# Power.net
KiCad netlist of a schematic drawn in Altium Designer
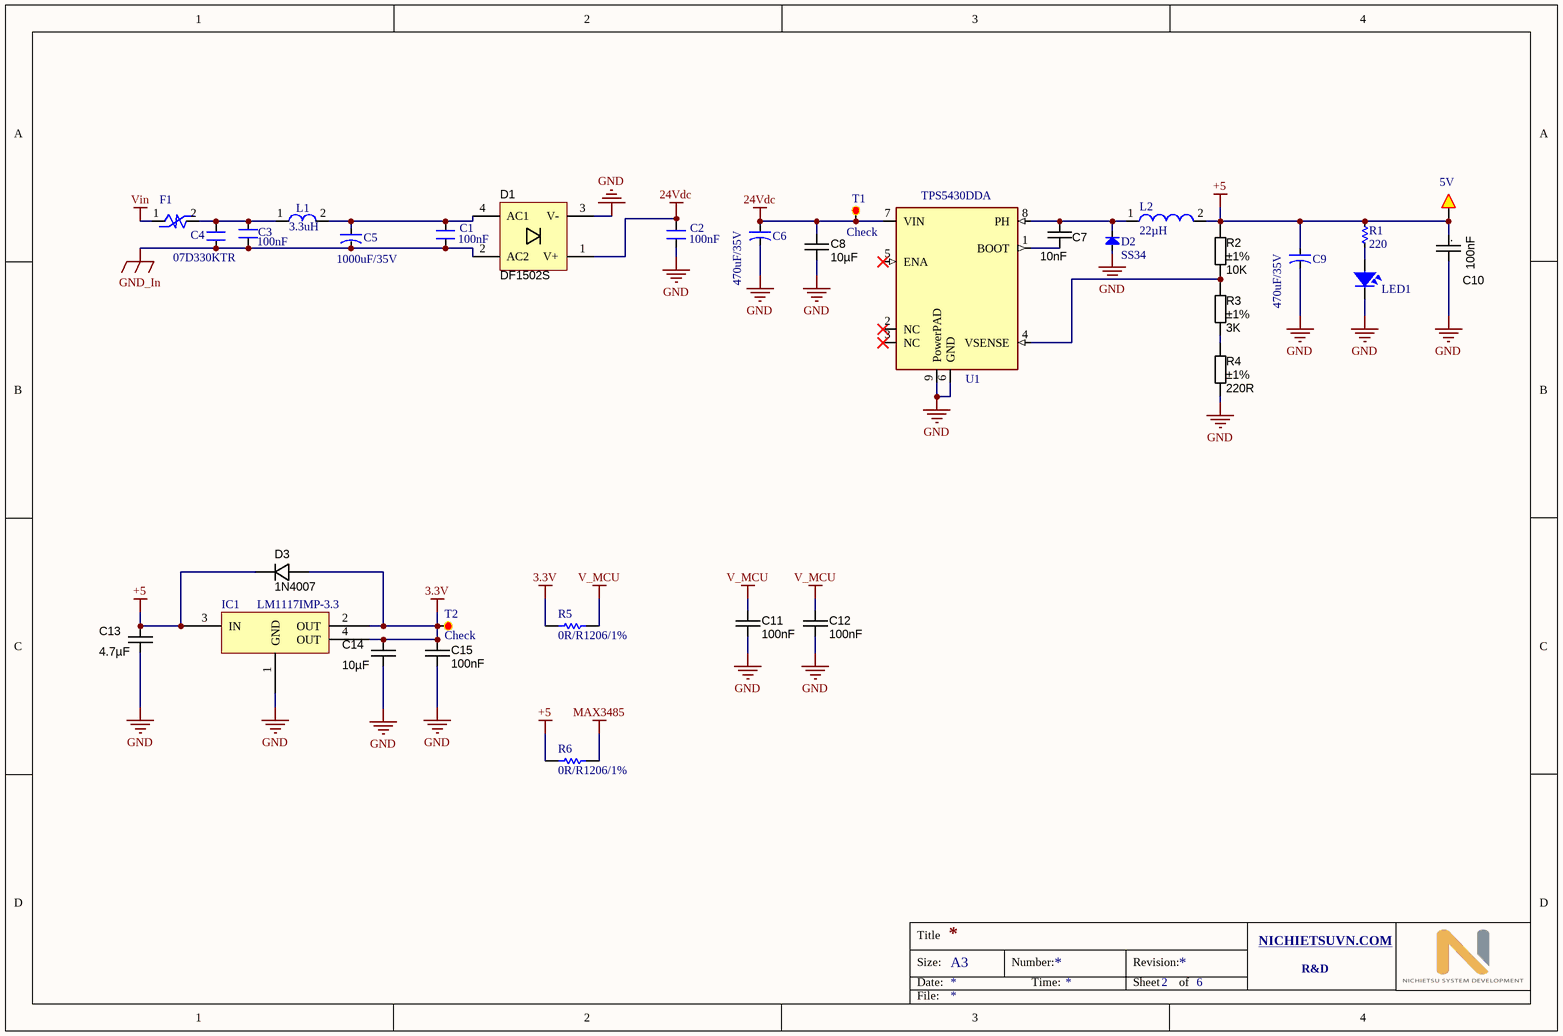
[diagram p0: Power.SchDoc]

(export (version "E")
  (design (tool "Eeschema 10.0.6"))
  (components
    (comp (ref "C1") (value "100nF") (footprint "CN-SMD-1206") (libsource (lib "thu vien 3d") (part "CN")))
    (comp (ref "C2") (value "100nF") (footprint "CN-SMD-1206") (libsource (lib "thu vien 3d") (part "CN")))
    (comp (ref "C3") (value "100nF") (footprint "CN2.5") (libsource (lib "thu vien 3d") (part "CN")))
    (comp (ref "C4") (value "07D330KTR") (footprint "CN2-T") (libsource (lib "thu vien 3d") (part "CN")))
    (comp (ref "C5")
      (value "1000uF/35V")
      (footprint "CA-ALU-5L")
      (description "Capacitor (Semiconductor SIM Model)")
      (fields (field (name "PUBLISHER") "Altium Limited"))
      (libsource (lib "thu vien 3d") (part "CN-ALU-DIP"))
    )
    (comp (ref "C6")
      (value "470uF/35V")
      (footprint "CA-ALU-6.3")
      (description "Capacitor (Semiconductor SIM Model)")
      (fields (field (name "PUBLISHER") "Altium Limited"))
      (libsource (lib "thu vien 3d") (part "CN-ALU-DIP"))
    )
    (comp (ref "C7")
      (value "10nF")
      (footprint "CAPC1608X90N")
      (description "10000pF ±10% 50V Ceramic Capacitor X7R 0603 (1608 Metric)")
      (fields (field (name "TOLERANCE") "±10%"))
      (libsource (lib "SangMV") (part "CAPC_10000pF_0603_50V_10%"))
    )
    (comp (ref "C8")
      (value "10µF")
      (footprint "CAPC2012X135N")
      (description "10µF ±10% 50V Ceramic Capacitor X7R 1206 (3216 Metric)")
      (fields (field (name "TOLERANCE") "±10%") (field (name "MANUFACTURER PART NUMBER") "TMK316AB7106KLHT"))
      (libsource (lib "All Library") (part "CAPC_10uF_0805_X7R_25V_10%"))
    )
    (comp (ref "C9")
      (value "470uF/35V")
      (footprint "CA-ALU-6.3")
      (description "Capacitor (Semiconductor SIM Model)")
      (fields (field (name "PUBLISHER") "Altium Limited"))
      (libsource (lib "thu vien 3d") (part "CN-ALU-DIP"))
    )
    (comp (ref "C10")
      (value "100nF")
      (footprint "CAPC2012X135N")
      (description "0.1µF ±10% 50V Ceramic Capacitor X7R 0805 (2012 Metric)")
      (fields (field (name "TOLERANCE") "±10%") (field (name "MANUFACTURER PART NUMBER") "CL21B104KBFXPJE"))
      (libsource (lib "SangMV") (part "CAPC_100nF_0805_X7R_50V_10%"))
    )
    (comp (ref "C11")
      (value "100nF")
      (footprint "CAPC1608X90N")
      (description "0.1µF ±10% 50V Ceramic Capacitor X7R 0603 (1608 Metric)")
      (fields (field (name "TOLERANCE") "±10%"))
      (libsource (lib "All Library") (part "CAPC_100nF_0603_X7R_50V_10%"))
    )
    (comp (ref "C12")
      (value "100nF")
      (footprint "CAPC1608X90N")
      (description "0.1µF ±10% 50V Ceramic Capacitor X7R 0603 (1608 Metric)")
      (fields (field (name "TOLERANCE") "±10%"))
      (libsource (lib "All Library") (part "CAPC_100nF_0603_X7R_50V_10%"))
    )
    (comp (ref "C13")
      (value "4.7µF")
      (footprint "CAPC2012X135N")
      (description "4.7µF ±10% 50V Ceramic Capacitor X7R 0805 (2012 Metric)")
      (fields
        (field (name "TOLERANCE") "±10%")
        (field (name "MANUFACTURER PART NUMBER") "CGA4J1X7R1H475K125AE")
      )
      (libsource (lib "All Library") (part "CAPC_4.7uF_0805_X7R_50V_10%"))
    )
    (comp (ref "C14")
      (value "10µF")
      (footprint "CAPC2012X135N")
      (description "4.7µF ±10% 50V Ceramic Capacitor X7R 0805 (2012 Metric)")
      (fields
        (field (name "TOLERANCE") "±10%")
        (field (name "MANUFACTURER PART NUMBER") "CGA4J1X7R1H475K125AE")
      )
      (libsource (lib "All Library") (part "CAPC_4.7uF_0805_X7R_50V_10%"))
    )
    (comp (ref "C15")
      (value "100nF")
      (footprint "CAPC1608X90N")
      (description "0.1µF ±10% 50V Ceramic Capacitor X7R 0603 (1608 Metric)")
      (fields (field (name "TOLERANCE") "±10%"))
      (libsource (lib "All Library") (part "CAPC_100nF_0603_X7R_50V_10%"))
    )
    (comp (ref "Check1")
      (value "5V")
      (footprint "SMD-2")
      (description "WR-PHD 2.54 mm Angled Socket Header")
      (fields
        (field (name "MANUFACTURER") "Würth Elektronik eiSos GmbH")
        (field (name "PARTNO") "613002143121")
        (field (name "CREATED BY") "Karrer Zheng")
      )
      (libsource (lib "Nichietsuvn") (part "Test"))
    )
    (comp (ref "D1")
      (value "DF1502S")
      (footprint "DIODE_DF_S")
      (description "Bridge Rectifier Single Phase Standard 200V Surface Mount DF-S")
      (libsource (lib "PCB_ESP32_Extern") (part "DIODE_DF1502S"))
    )
    (comp (ref "D2")
      (value "SS34")
      (footprint "DIO-SMD-106")
      (description "Default Diode")
      (fields (field (name "PUBLISHER") "Altium Limited"))
      (libsource (lib "thu vien 3d") (part "Diode SMD"))
    )
    (comp (ref "D3")
      (value "1N4007")
      (footprint "DO-214AC")
      (description "Diode  Standard Rectifier SMD 1000V 1A SMA")
      (libsource (lib "All Library") (part "DIODE_1N4007"))
    )
    (comp (ref "F1") (value "RUEF185") (footprint "RUEF165") (libsource (lib "All Library") (part "RUEF185")))
    (comp (ref "IC1")
      (value "LM1117IMP-3.3")
      (footprint "SOT223")
      (description "Linear Voltage Regulator IC  1 Output  800mA SOT-223")
      (fields
        (field (name "MANUFACTURER") "Texas Instruments")
        (field (name "MANUFACTURER PART NUMBER") "LM1117IMP-3.3/NOPB")
      )
      (libsource (lib "All Library") (part "IC_LM1117IMP-3.3"))
    )
    (comp (ref "L1")
      (value "3.3uH")
      (footprint "L-SMD-M-7.3x4.5")
      (fields
        (field (name "PARTNO") "78477010")
        (field (name "MANUFACTURER") "Wurth Elektronik")
        (field (name "CREATED BY") "Baojun Chen")
      )
      (libsource (lib "thu vien 3d") (part "L-SMD-1"))
    )
    (comp (ref "L2")
      (value "22µH")
      (footprint "IND_COIL_8D43")
      (description "22µH Shielded Wirewound Inductor 950mA 380mOhm Max Nonstandard")
      (libsource (lib "SangMV") (part "INDC_SMD_22uH_8D43"))
    )
    (comp (ref "LED1")
      (value "LED")
      (footprint "LED-0805-Blue")
      (libsource (lib "thu vien 3d") (part "LED SMD"))
    )
    (comp (ref "R1")
      (value "220")
      (footprint "RES-SMD-0603")
      (description "Resistor")
      (fields
        (field (name "MANUFACTURER") "Generic Components")
        (field (name "PUBLISHER") "Altium Hobart Technology Centre")
      )
      (libsource (lib "thu vien 3d") (part "Res-SMD"))
    )
    (comp (ref "R2")
      (value "10K")
      (footprint "RESC1608X55N")
      (fields
        (field (name "MANUFACTURER") "Stackpole Electronics Inc")
        (field (name "MANUFACTURER PART NUMBER") "RMCF0603FT10K0")
        (field (name "TOLERANCE") "±1%")
        (field (name "Comment") "10K_0603_1%")
      )
      (libsource (lib "SangMV") (part "RES_10K_0603_1%"))
    )
    (comp (ref "R3")
      (value "3K")
      (footprint "RESC1608X55N")
      (description "3 kOhms ±1% 0.1W, 1/10W Chip Resistor 0603 (1608 Metric) Automotive AEC-Q200 Thick Film")
      (fields
        (field (name "MANUFACTURER") "Stackpole Electronics Inc")
        (field (name "MANUFACTURER PART NUMBER") "RMCF0603FT3K00")
        (field (name "TOLERANCE") "±1%")
      )
      (libsource (lib "SangMV") (part "RES_3K_0603_1%"))
    )
    (comp (ref "R4")
      (value "220R")
      (footprint "RESC1608X55N")
      (description "220 Ohms ±1% 0.1W, 1/10W Chip Resistor 0603 (1608 Metric) Automotive AEC-Q200 Thick Film")
      (fields
        (field (name "MANUFACTURER") "Stackpole Electronics Inc")
        (field (name "MANUFACTURER PART NUMBER") "RMCF0603FT220R")
        (field (name "TOLERANCE") "±1%")
      )
      (libsource (lib "SangMV") (part "RES_220R_0603_1%"))
    )
    (comp (ref "R5")
      (value "0R/R1206/1%")
      (footprint "R1206")
      (description "RES SMD 0.0 OHM JUMPER 1/4W 1206")
      (fields
        (field (name "MANUFACTURER") "Bourns Inc.")
        (field (name "MANUFACTURER PART NUMBER") "CR1206-J/-000ELF")
      )
      (libsource (lib "All Library") (part "RES_0R/R1206/1%"))
    )
    (comp (ref "R6")
      (value "0R/R1206/1%")
      (footprint "R1206")
      (description "RES SMD 0.0 OHM JUMPER 1/4W 1206")
      (fields
        (field (name "MANUFACTURER") "Bourns Inc.")
        (field (name "MANUFACTURER PART NUMBER") "CR1206-J/-000ELF")
      )
      (libsource (lib "All Library") (part "RES_0R/R1206/1%"))
    )
    (comp (ref "T1")
      (value "Check")
      (footprint "SMD_1.5")
      (description "WR-PHD 2.54 mm Angled Socket Header")
      (fields
        (field (name "MANUFACTURER") "Würth Elektronik eiSos GmbH")
        (field (name "PARTNO") "613002143121")
        (field (name "CREATED BY") "Karrer Zheng")
      )
      (libsource (lib "All Library") (part "Test"))
    )
    (comp (ref "T2")
      (value "Check")
      (footprint "SMD_1.5")
      (description "WR-PHD 2.54 mm Angled Socket Header")
      (fields
        (field (name "MANUFACTURER") "Würth Elektronik eiSos GmbH")
        (field (name "PARTNO") "613002143121")
        (field (name "CREATED BY") "Karrer Zheng")
      )
      (libsource (lib "All Library") (part "Test"))
    )
    (comp (ref "U1")
      (value "TPS5430DDA")
      (footprint "TPS5430")
      (libsource (lib "Nichietsuvn") (part "TPS5430DDA"))
    )
  )
  (nets
    (net (code "1") (name "+5") (class "Default")
      (node (ref "C10") (pin "1") (pintype "passive"))
      (node (ref "C13") (pin "2") (pintype "passive"))
      (node (ref "C9") (pin "1") (pinfunction "1_1") (pintype "passive"))
      (node (ref "Check1") (pin "1") (pinfunction "1_1") (pintype "passive"))
      (node (ref "D3") (pin "C") (pinfunction "C_C") (pintype "passive"))
      (node (ref "IC1") (pin "3") (pinfunction "IN_3") (pintype "passive"))
      (node (ref "L2") (pin "2") (pinfunction "2_2") (pintype "passive"))
      (node (ref "R1") (pin "1") (pinfunction "1_1") (pintype "passive"))
      (node (ref "R2") (pin "2") (pinfunction "2_2") (pintype "passive"))
      (node (ref "R6") (pin "1") (pinfunction "1_1") (pintype "passive"))
    )
    (net (code "2") (name "3.3V") (class "Default")
      (node (ref "C14") (pin "2") (pintype "passive"))
      (node (ref "C15") (pin "1") (pintype "passive"))
      (node (ref "D3") (pin "A") (pinfunction "A_A") (pintype "passive"))
      (node (ref "IC1") (pin "2") (pinfunction "OUT_2") (pintype "passive"))
      (node (ref "IC1") (pin "4") (pinfunction "OUT_4") (pintype "passive"))
      (node (ref "R5") (pin "1") (pinfunction "1_1") (pintype "passive"))
      (node (ref "T2") (pin "1") (pinfunction "1_1") (pintype "passive"))
    )
    (net (code "3") (name "24Vdc") (class "Default")
      (node (ref "C2") (pin "2") (pinfunction "2_2") (pintype "passive"))
      (node (ref "C6") (pin "1") (pinfunction "1_1") (pintype "passive"))
      (node (ref "C8") (pin "2") (pintype "passive"))
      (node (ref "D1") (pin "1") (pinfunction "V+_1") (pintype "passive"))
      (node (ref "T1") (pin "1") (pinfunction "1_1") (pintype "passive"))
      (node (ref "U1") (pin "7") (pinfunction "VIN_7") (pintype "power_in"))
    )
    (net (code "4") (name "GND") (class "Default")
      (node (ref "C10") (pin "2") (pintype "passive"))
      (node (ref "C11") (pin "2") (pintype "passive"))
      (node (ref "C12") (pin "2") (pintype "passive"))
      (node (ref "C13") (pin "1") (pintype "passive"))
      (node (ref "C14") (pin "1") (pintype "passive"))
      (node (ref "C15") (pin "2") (pintype "passive"))
      (node (ref "C2") (pin "1") (pinfunction "1_1") (pintype "passive"))
      (node (ref "C6") (pin "2") (pinfunction "2_2") (pintype "passive"))
      (node (ref "C8") (pin "1") (pintype "passive"))
      (node (ref "C9") (pin "2") (pinfunction "2_2") (pintype "passive"))
      (node (ref "D1") (pin "3") (pinfunction "V-_3") (pintype "passive"))
      (node (ref "D2") (pin "1") (pinfunction "A_1") (pintype "passive"))
      (node (ref "IC1") (pin "1") (pinfunction "GND_1") (pintype "passive"))
      (node (ref "LED1") (pin "2") (pinfunction "2_2") (pintype "passive"))
      (node (ref "R4") (pin "1") (pinfunction "1_1") (pintype "passive"))
      (node (ref "U1") (pin "6") (pinfunction "GND_6") (pintype "power_in"))
      (node (ref "U1") (pin "9") (pinfunction "PowerPAD_9") (pintype "power_in"))
    )
    (net (code "5") (name "GND_In") (class "Default")
      (node (ref "C1") (pin "1") (pinfunction "1_1") (pintype "passive"))
      (node (ref "C3") (pin "1") (pinfunction "1_1") (pintype "passive"))
      (node (ref "C4") (pin "1") (pinfunction "1_1") (pintype "passive"))
      (node (ref "C5") (pin "2") (pinfunction "2_2") (pintype "passive"))
      (node (ref "D1") (pin "2") (pinfunction "AC2_2") (pintype "passive"))
    )
    (net (code "6") (name "MAX3485") (class "Default")
      (node (ref "R6") (pin "2") (pinfunction "2_2") (pintype "passive"))
    )
    (net (code "7") (name "Net-(C3-Pad2)") (class "Default")
      (node (ref "C3") (pin "2") (pinfunction "2_2") (pintype "passive"))
      (node (ref "C4") (pin "2") (pinfunction "2_2") (pintype "passive"))
      (node (ref "F1") (pin "2") (pinfunction "2_2") (pintype "passive"))
      (node (ref "L1") (pin "1") (pinfunction "1_1") (pintype "passive"))
    )
    (net (code "8") (name "Net-(D1-AC1)") (class "Default")
      (node (ref "C1") (pin "2") (pinfunction "2_2") (pintype "passive"))
      (node (ref "C5") (pin "1") (pinfunction "1_1") (pintype "passive"))
      (node (ref "D1") (pin "4") (pinfunction "AC1_4") (pintype "passive"))
      (node (ref "L1") (pin "2") (pinfunction "2_2") (pintype "passive"))
    )
    (net (code "9") (name "Net-(D2-K)") (class "Default")
      (node (ref "C7") (pin "2") (pintype "passive"))
      (node (ref "D2") (pin "2") (pinfunction "K_2") (pintype "passive"))
      (node (ref "L2") (pin "1") (pinfunction "1_1") (pintype "passive"))
      (node (ref "U1") (pin "8") (pinfunction "PH_8") (pintype "input"))
    )
    (net (code "10") (name "Net-(LED1-Pad1)") (class "Default")
      (node (ref "LED1") (pin "1") (pinfunction "1_1") (pintype "passive"))
      (node (ref "R1") (pin "2") (pinfunction "2_2") (pintype "passive"))
    )
    (net (code "11") (name "Net-(R3-Pad1)") (class "Default")
      (node (ref "R3") (pin "1") (pinfunction "1_1") (pintype "passive"))
      (node (ref "R4") (pin "2") (pinfunction "2_2") (pintype "passive"))
    )
    (net (code "12") (name "Net-(U1-BOOT)") (class "Default")
      (node (ref "C7") (pin "1") (pintype "passive"))
      (node (ref "U1") (pin "1") (pinfunction "BOOT_1") (pintype "output"))
    )
    (net (code "13") (name "Net-(U1-VSENSE)") (class "Default")
      (node (ref "R2") (pin "1") (pinfunction "1_1") (pintype "passive"))
      (node (ref "R3") (pin "2") (pinfunction "2_2") (pintype "passive"))
      (node (ref "U1") (pin "4") (pinfunction "VSENSE_4") (pintype "input"))
    )
    (net (code "14") (name "V_MCU") (class "Default")
      (node (ref "C11") (pin "1") (pintype "passive"))
      (node (ref "C12") (pin "1") (pintype "passive"))
      (node (ref "R5") (pin "2") (pinfunction "2_2") (pintype "passive"))
    )
    (net (code "15") (name "Vin") (class "Default")
      (node (ref "F1") (pin "1") (pinfunction "1_1") (pintype "passive"))
    )
    (net (code "16") (name "unconnected-(U1-ENA-Pad5)") (class "Default")
      (node (ref "U1") (pin "5") (pinfunction "ENA_5") (pintype "input+no_connect"))
    )
    (net (code "17") (name "unconnected-(U1-NC-Pad2)") (class "Default")
      (node (ref "U1") (pin "2") (pinfunction "NC_2") (pintype "passive+no_connect"))
    )
    (net (code "18") (name "unconnected-(U1-NC-Pad3)") (class "Default")
      (node (ref "U1") (pin "3") (pinfunction "NC_3") (pintype "passive+no_connect"))
    )
  )
)
